# Radio.net
KiCad netlist of a schematic drawn in Altium Designer
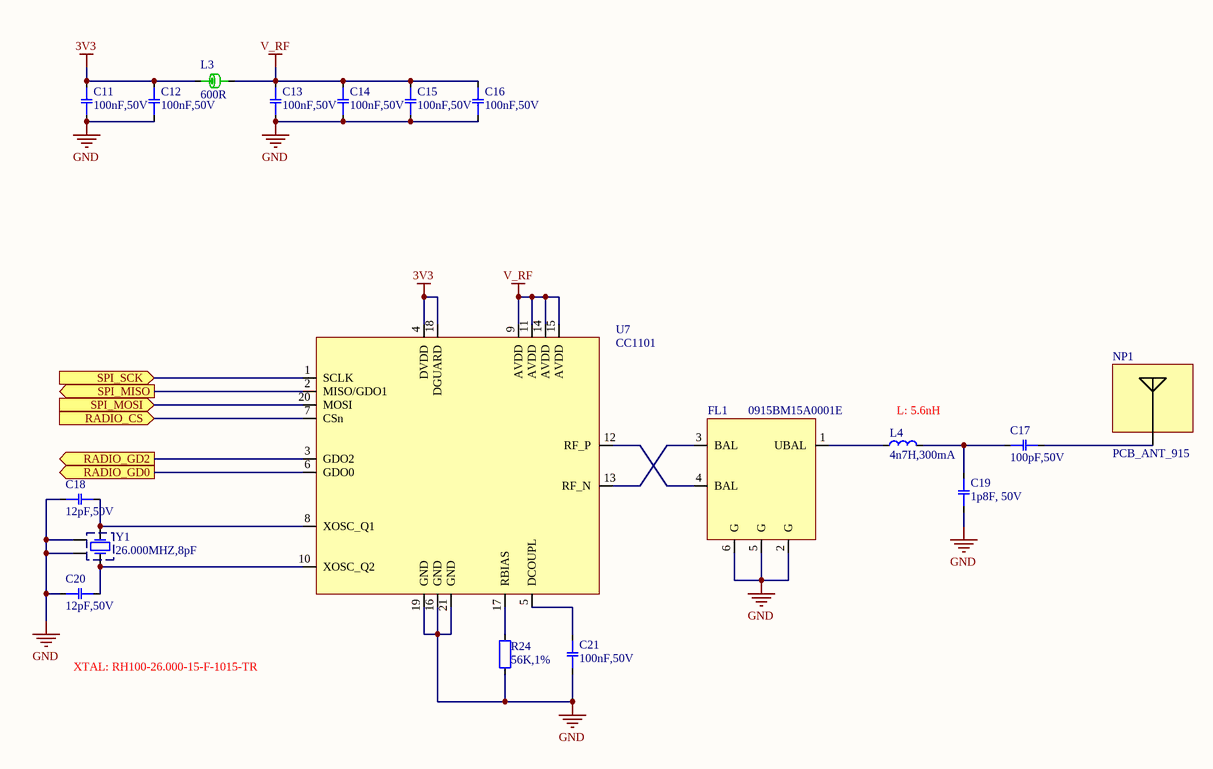
[diagram p0: Radio.SchDoc]

(export (version "E")
  (design (tool "Eeschema 10.0.6"))
  (components
    (comp (ref "C11")
      (value "100nF,50V")
      (footprint "CAPC1005X05N_0402")
      (description "CAP CER 0.1UF 50V X7R 0402")
      (fields (field (name "MANUFACTURER") "Taiyo Yuden") (field (name "TOLERANCE") "10%"))
      (libsource (lib "library") (part "CAP-NP_1"))
    )
    (comp (ref "C12")
      (value "100nF,50V")
      (footprint "CAPC1005X05N_0402")
      (description "CAP CER 0.1UF 50V X7R 0402")
      (fields (field (name "MANUFACTURER") "Taiyo Yuden") (field (name "TOLERANCE") "10%"))
      (libsource (lib "library") (part "CAP-NP_1"))
    )
    (comp (ref "C13")
      (value "100nF,50V")
      (footprint "CAPC1005X05N_0402")
      (description "CAP CER 0.1UF 50V X7R 0402")
      (fields (field (name "MANUFACTURER") "Taiyo Yuden") (field (name "TOLERANCE") "10%"))
      (libsource (lib "library") (part "CAP-NP_1"))
    )
    (comp (ref "C14")
      (value "100nF,50V")
      (footprint "CAPC1005X05N_0402")
      (description "CAP CER 0.1UF 50V X7R 0402")
      (fields (field (name "MANUFACTURER") "Taiyo Yuden") (field (name "TOLERANCE") "10%"))
      (libsource (lib "library") (part "CAP-NP_1"))
    )
    (comp (ref "C15")
      (value "100nF,50V")
      (footprint "CAPC1005X05N_0402")
      (description "CAP CER 0.1UF 50V X7R 0402")
      (fields (field (name "MANUFACTURER") "Taiyo Yuden") (field (name "TOLERANCE") "10%"))
      (libsource (lib "library") (part "CAP-NP_1"))
    )
    (comp (ref "C16")
      (value "100nF,50V")
      (footprint "CAPC1005X05N_0402")
      (description "CAP CER 0.1UF 50V X7R 0402")
      (fields (field (name "MANUFACTURER") "Taiyo Yuden") (field (name "TOLERANCE") "10%"))
      (libsource (lib "library") (part "CAP-NP_1"))
    )
    (comp (ref "C17")
      (value "100pF,50V")
      (footprint "CAPC1005X05N_0402")
      (description "CAP CER 100PF 50V 5% NP0 0402")
      (fields
        (field (name "MANUFACTURER") "Murata Electronics North America")
        (field (name "TOLERANCE") "5%")
      )
      (libsource (lib "library") (part "CAP-NP_1"))
    )
    (comp (ref "C18")
      (value "12pF,50V")
      (footprint "CAPC1005X05N_0402")
      (description "CAP CER 12PF 50V 5% NP0 0402")
      (fields
        (field (name "MANUFACTURER") "Murata Electronics North America")
        (field (name "TOLERANCE") "5%")
      )
      (libsource (lib "library") (part "CAP-NP_1"))
    )
    (comp (ref "C19")
      (value "1p8F, 50V")
      (footprint "CAPC1005X05N_0402")
      (description "CAP CER 1.8PF 50V C0G/NP0 0402")
      (fields
        (field (name "MANUFACTURER") "Murata Electronics North America")
        (field (name "TOLERANCE") "±0.1pF")
      )
      (libsource (lib "library") (part "CAP-NP_1"))
    )
    (comp (ref "C20")
      (value "12pF,50V")
      (footprint "CAPC1005X05N_0402")
      (description "CAP CER 12PF 50V 5% NP0 0402")
      (fields
        (field (name "MANUFACTURER") "Murata Electronics North America")
        (field (name "TOLERANCE") "5%")
      )
      (libsource (lib "library") (part "CAP-NP_1"))
    )
    (comp (ref "C21")
      (value "100nF,50V")
      (footprint "CAPC1005X05N_0402")
      (description "CAP CER 0.1UF 50V X7R 0402")
      (fields (field (name "MANUFACTURER") "Taiyo Yuden") (field (name "TOLERANCE") "10%"))
      (libsource (lib "library") (part "CAP-NP_1"))
    )
    (comp (ref "FL1")
      (value "0915BM15A0001E")
      (footprint "FLTR65P200X125-6N_0805")
      (description "BALUN 902MHZ-928MHZ 0805")
      (fields (field (name "MANUFACTURER") "Johanson Technology Inc"))
      (libsource (lib "library") (part "____BM15A0001E"))
    )
    (comp (ref "L3")
      (value "600R")
      (footprint "INDC1608X10N_0603")
      (description "FERRITE BEAD 600 OHM 0603 1LN")
      (fields
        (field (name "MANUFACTURER") "Wurth Electronics Inc")
        (field (name "MANUFACTURER PART NUMBER") "742792651")
      )
      (libsource (lib "library") (part "FERRITE"))
    )
    (comp (ref "L4")
      (value "4n7H,300mA")
      (footprint "INDC1005X04N_0402")
      (description "INDUCTOR 4.7NH 300MA 0402")
      (fields
        (field (name "MANUFACTURER") "Murata Electronics North America")
        (field (name "MANUFACTURER PART NUMBER") "LQG15HS4N7S02D")
      )
      (libsource (lib "library") (part "INDUCTOR_1"))
    )
    (comp (ref "NP1")
      (value "PCB_ANT_915")
      (footprint "ANT_PCB_915")
      (libsource (lib "Common") (part "PCB_ANT_915"))
    )
    (comp (ref "R24")
      (value "56K,1%")
      (footprint "RESC1005X04N_0402")
      (description "RES 56.0K OHM 1/16W 1% 0402 SMD")
      (fields (field (name "MANUFACTURER") "Yageo") (field (name "POWER") "0.063W"))
      (libsource (lib "library") (part "RESISTOR_1"))
    )
    (comp (ref "U7")
      (value "CC1101")
      (footprint "QFN50P400X400X75-20N_20QFN")
      (description "IC RF TXRX ISM<1GHZ 20VFQFN")
      (fields
        (field (name "MANUFACTURER") "Texas Instruments")
        (field (name "MANUFACTURER PART NUMBER") "CC1101RGPR")
      )
      (libsource (lib "library") (part "CC1101"))
    )
    (comp (ref "Y1")
      (value "26.000MHZ,8pF")
      (footprint "XTAL_NX3225SA")
      (description "CRYSTAL 26MHZ 8PF SMD")
      (fields
        (field (name "MANUFACTURER") "NDK")
        (field (name "MANUFACTURER PART NUMBER") "NX3225SA-26.000000MHZ-STD-CSR-1")
      )
      (libsource (lib "library") (part "XTAL_2"))
    )
  )
  (nets
    (net (code "1") (name "/RADIO_CS") (class "Default")
      (node (ref "U7") (pin "7") (pinfunction "CSn_7") (pintype "passive"))
    )
    (net (code "2") (name "/RADIO_GD0") (class "Default")
      (node (ref "U7") (pin "6") (pinfunction "GDO0_6") (pintype "passive"))
    )
    (net (code "3") (name "/RADIO_GD2") (class "Default")
      (node (ref "U7") (pin "3") (pinfunction "GDO2_3") (pintype "passive"))
    )
    (net (code "4") (name "/SPI_MISO") (class "Default")
      (node (ref "U7") (pin "2") (pinfunction "MISO/GDO1_2") (pintype "passive"))
    )
    (net (code "5") (name "/SPI_MOSI") (class "Default")
      (node (ref "U7") (pin "20") (pinfunction "MOSI_20") (pintype "passive"))
    )
    (net (code "6") (name "/SPI_SCK") (class "Default")
      (node (ref "U7") (pin "1") (pinfunction "SCLK_1") (pintype "passive"))
    )
    (net (code "7") (name "3V3") (class "Default")
      (node (ref "C11") (pin "2") (pinfunction "2_2") (pintype "passive"))
      (node (ref "C12") (pin "2") (pinfunction "2_2") (pintype "passive"))
      (node (ref "L3") (pin "1") (pintype "passive"))
      (node (ref "U7") (pin "18") (pinfunction "DGUARD_18") (pintype "passive"))
      (node (ref "U7") (pin "4") (pinfunction "DVDD_4") (pintype "passive"))
    )
    (net (code "8") (name "GND") (class "Default")
      (node (ref "C11") (pin "1") (pinfunction "1_1") (pintype "passive"))
      (node (ref "C12") (pin "1") (pinfunction "1_1") (pintype "passive"))
      (node (ref "C13") (pin "1") (pinfunction "1_1") (pintype "passive"))
      (node (ref "C14") (pin "1") (pinfunction "1_1") (pintype "passive"))
      (node (ref "C15") (pin "1") (pinfunction "1_1") (pintype "passive"))
      (node (ref "C16") (pin "1") (pinfunction "1_1") (pintype "passive"))
      (node (ref "C18") (pin "1") (pinfunction "1_1") (pintype "passive"))
      (node (ref "C19") (pin "1") (pinfunction "1_1") (pintype "passive"))
      (node (ref "C20") (pin "1") (pinfunction "1_1") (pintype "passive"))
      (node (ref "C21") (pin "1") (pinfunction "1_1") (pintype "passive"))
      (node (ref "FL1") (pin "2") (pinfunction "G_2") (pintype "passive"))
      (node (ref "FL1") (pin "5") (pinfunction "G_5") (pintype "passive"))
      (node (ref "FL1") (pin "6") (pinfunction "G_6") (pintype "passive"))
      (node (ref "R24") (pin "1") (pinfunction "1_1") (pintype "passive"))
      (node (ref "U7") (pin "16") (pinfunction "GND_16") (pintype "passive"))
      (node (ref "U7") (pin "19") (pinfunction "GND_19") (pintype "passive"))
      (node (ref "U7") (pin "21") (pinfunction "GND_21") (pintype "passive"))
      (node (ref "Y1") (pin "2") (pinfunction "2_2") (pintype "passive"))
      (node (ref "Y1") (pin "4") (pinfunction "4_4") (pintype "passive"))
    )
    (net (code "9") (name "Net-(C17-Pad1)") (class "Default")
      (node (ref "C17") (pin "1") (pinfunction "1_1") (pintype "passive"))
      (node (ref "C19") (pin "2") (pinfunction "2_2") (pintype "passive"))
      (node (ref "L4") (pin "2") (pinfunction "2_2") (pintype "passive"))
    )
    (net (code "10") (name "Net-(FL1-UBAL)") (class "Default")
      (node (ref "FL1") (pin "1") (pinfunction "UBAL_1") (pintype "passive"))
      (node (ref "L4") (pin "1") (pinfunction "1_1") (pintype "passive"))
    )
    (net (code "11") (name "Net-(NP1-ANT)") (class "Default")
      (node (ref "C17") (pin "2") (pinfunction "2_2") (pintype "passive"))
      (node (ref "NP1") (pin "1") (pinfunction "ANT_1") (pintype "passive"))
    )
    (net (code "12") (name "Net-(U7-DCOUPL)") (class "Default")
      (node (ref "C21") (pin "2") (pinfunction "2_2") (pintype "passive"))
      (node (ref "U7") (pin "5") (pinfunction "DCOUPL_5") (pintype "passive"))
    )
    (net (code "13") (name "Net-(U7-RBIAS)") (class "Default")
      (node (ref "R24") (pin "2") (pinfunction "2_2") (pintype "passive"))
      (node (ref "U7") (pin "17") (pinfunction "RBIAS_17") (pintype "passive"))
    )
    (net (code "14") (name "Net-(U7-RF_N)") (class "Default")
      (node (ref "FL1") (pin "3") (pinfunction "BAL_3") (pintype "passive"))
      (node (ref "U7") (pin "13") (pinfunction "RF_N_13") (pintype "passive"))
    )
    (net (code "15") (name "Net-(U7-RF_P)") (class "Default")
      (node (ref "FL1") (pin "4") (pinfunction "BAL_4") (pintype "passive"))
      (node (ref "U7") (pin "12") (pinfunction "RF_P_12") (pintype "passive"))
    )
    (net (code "16") (name "Net-(U7-XOSC_Q1)") (class "Default")
      (node (ref "C18") (pin "2") (pinfunction "2_2") (pintype "passive"))
      (node (ref "U7") (pin "8") (pinfunction "XOSC_Q1_8") (pintype "passive"))
      (node (ref "Y1") (pin "1") (pinfunction "1_1") (pintype "passive"))
    )
    (net (code "17") (name "Net-(U7-XOSC_Q2)") (class "Default")
      (node (ref "C20") (pin "2") (pinfunction "2_2") (pintype "passive"))
      (node (ref "U7") (pin "10") (pinfunction "XOSC_Q2_10") (pintype "passive"))
      (node (ref "Y1") (pin "3") (pinfunction "3_3") (pintype "passive"))
    )
    (net (code "18") (name "V_RF") (class "Default")
      (node (ref "C13") (pin "2") (pinfunction "2_2") (pintype "passive"))
      (node (ref "C14") (pin "2") (pinfunction "2_2") (pintype "passive"))
      (node (ref "C15") (pin "2") (pinfunction "2_2") (pintype "passive"))
      (node (ref "C16") (pin "2") (pinfunction "2_2") (pintype "passive"))
      (node (ref "L3") (pin "2") (pintype "passive"))
      (node (ref "U7") (pin "11") (pinfunction "AVDD_11") (pintype "passive"))
      (node (ref "U7") (pin "14") (pinfunction "AVDD_14") (pintype "passive"))
      (node (ref "U7") (pin "15") (pinfunction "AVDD_15") (pintype "passive"))
      (node (ref "U7") (pin "9") (pinfunction "AVDD_9") (pintype "passive"))
    )
  )
)
